# power-sheet.net
KiCad netlist of a schematic drawn in Altium Designer
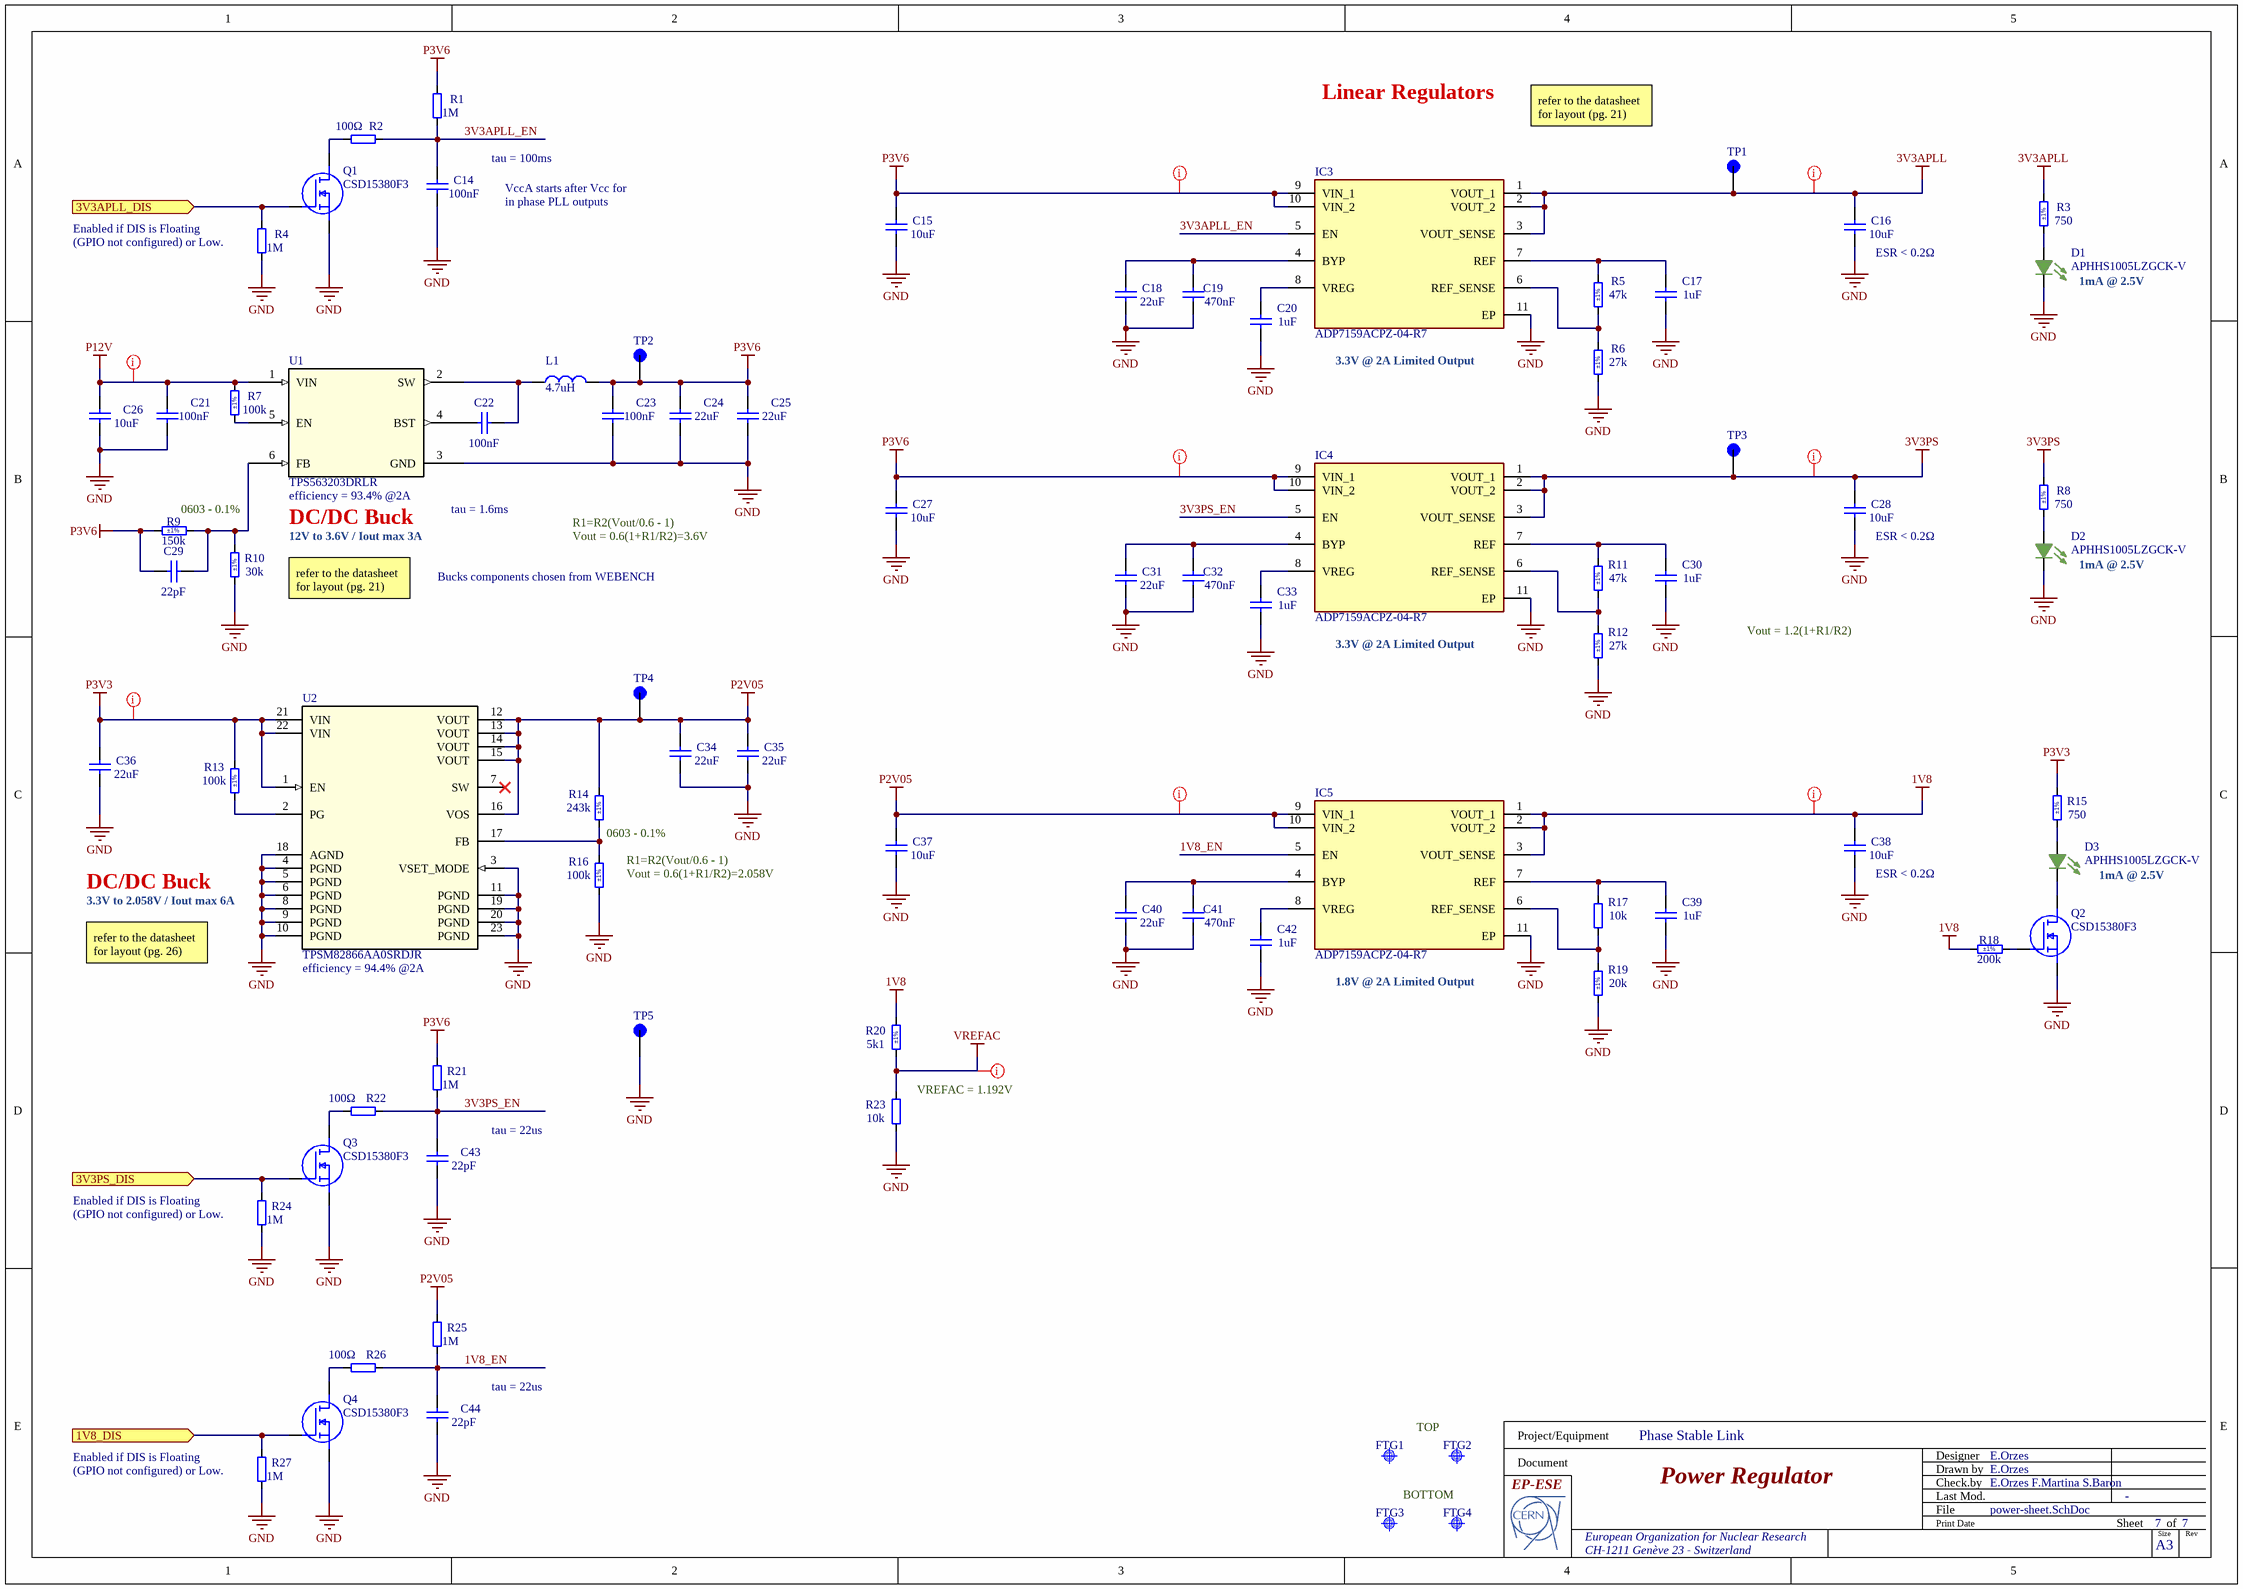
[diagram p0: power-sheet.SchDoc]

(export (version "E")
  (design (tool "Eeschema 10.0.6"))
  (components
    (comp (ref "C14")
      (value "100nF")
      (footprint "MURATA_HI_DENSITY_0201")
      (description "GRM033R61C104KE14")
      (libsource (lib "schLib") (part "C0201-100nF-high-density"))
    )
    (comp (ref "C15")
      (value "10uF")
      (footprint "CAPC1608X87N")
      (description "C1608X5R1E106M080AC")
      (fields
        (field (name "PART NUMBER") "CC0603_10UF_6.3V_20%_X5R")
        (field (name "VOLTAGE") "6.3V")
        (field (name "AUTHOR") "CERN DEM JLC")
      )
      (libsource (lib "Capacitors") (part "Capacitor - non polarized"))
    )
    (comp (ref "C16")
      (value "10uF")
      (footprint "CAPC1608X87N")
      (description "C1608X5R1E106M080AC")
      (fields
        (field (name "PART NUMBER") "CC0603_10UF_6.3V_20%_X5R")
        (field (name "VOLTAGE") "6.3V")
        (field (name "AUTHOR") "CERN DEM JLC")
      )
      (libsource (lib "Capacitors") (part "Capacitor - non polarized"))
    )
    (comp (ref "C17")
      (value "1uF")
      (footprint "CAPC1005X55N")
      (description "GRM153B30J105ME15")
      (fields
        (field (name "PART NUMBER") "CC0402_1UF_16V_10%_X5R")
        (field (name "VOLTAGE") "16V")
        (field (name "AUTHOR") "CERN DEM JLC")
      )
      (libsource (lib "Capacitors") (part "Capacitor - non polarized"))
    )
    (comp (ref "C18")
      (value "22uF")
      (footprint "MURATA_HI_DENSITY_0402_CAP")
      (description "GRM155R60J226ME11")
      (libsource (lib "schLib") (part "C0402-22uF-high-density"))
    )
    (comp (ref "C19")
      (value "470nF")
      (footprint "CAPC0510X04N")
      (description "LLL153C70G474ME17")
      (libsource (lib "auxiliary_library") (part "Capacitor - non polarized"))
    )
    (comp (ref "C20")
      (value "1uF")
      (footprint "CAPC1005X55N")
      (description "GRM153B30J105ME15")
      (fields
        (field (name "PART NUMBER") "CC0402_1UF_16V_10%_X5R")
        (field (name "VOLTAGE") "16V")
        (field (name "AUTHOR") "CERN DEM JLC")
      )
      (libsource (lib "Capacitors") (part "Capacitor - non polarized"))
    )
    (comp (ref "C21")
      (value "100nF")
      (footprint "MURATA_HI_DENSITY_0402_CAP")
      (description "GRM155R71E104KE14")
      (libsource (lib "schLib") (part "C0402-22uF-high-density"))
    )
    (comp (ref "C22")
      (value "100nF")
      (footprint "MURATA_HI_DENSITY_0402_CAP")
      (description "GRM155R71E104KE14")
      (libsource (lib "schLib") (part "C0402-22uF-high-density"))
    )
    (comp (ref "C23")
      (value "100nF")
      (footprint "MURATA_HI_DENSITY_0402_CAP")
      (description "GRM155R71E104KE14")
      (libsource (lib "schLib") (part "C0402-22uF-high-density"))
    )
    (comp (ref "C24")
      (value "22uF")
      (footprint "MURATA_HI_DENSITY_0402_CAP")
      (description "GRM155R60J226ME11")
      (libsource (lib "schLib") (part "C0402-22uF-high-density"))
    )
    (comp (ref "C25")
      (value "22uF")
      (footprint "MURATA_HI_DENSITY_0402_CAP")
      (description "GRM155R60J226ME11")
      (libsource (lib "schLib") (part "C0402-22uF-high-density"))
    )
    (comp (ref "C26")
      (value "10uF")
      (footprint "CAPC1608X87N")
      (description "C1608X5R1E106M080AC")
      (fields
        (field (name "PART NUMBER") "CC0603_10UF_6.3V_20%_X5R")
        (field (name "VOLTAGE") "6.3V")
        (field (name "AUTHOR") "CERN DEM JLC")
      )
      (libsource (lib "Capacitors") (part "Capacitor - non polarized"))
    )
    (comp (ref "C27")
      (value "10uF")
      (footprint "CAPC1608X87N")
      (description "C1608X5R1E106M080AC")
      (fields
        (field (name "PART NUMBER") "CC0603_10UF_6.3V_20%_X5R")
        (field (name "VOLTAGE") "6.3V")
        (field (name "AUTHOR") "CERN DEM JLC")
      )
      (libsource (lib "Capacitors") (part "Capacitor - non polarized"))
    )
    (comp (ref "C28")
      (value "10uF")
      (footprint "CAPC1608X87N")
      (description "C1608X5R1E106M080AC")
      (fields
        (field (name "PART NUMBER") "CC0603_10UF_6.3V_20%_X5R")
        (field (name "VOLTAGE") "6.3V")
        (field (name "AUTHOR") "CERN DEM JLC")
      )
      (libsource (lib "Capacitors") (part "Capacitor - non polarized"))
    )
    (comp (ref "C29")
      (value "22pF")
      (footprint "MURATA_HI_DENSITY_0402_CAP")
      (description "C0402C220J4GACTU")
      (libsource (lib "schLib") (part "C0402-22uF-high-density"))
    )
    (comp (ref "C30")
      (value "1uF")
      (footprint "CAPC1005X55N")
      (description "GRM153B30J105ME15")
      (fields
        (field (name "PART NUMBER") "CC0402_1UF_16V_10%_X5R")
        (field (name "VOLTAGE") "16V")
        (field (name "AUTHOR") "CERN DEM JLC")
      )
      (libsource (lib "Capacitors") (part "Capacitor - non polarized"))
    )
    (comp (ref "C31")
      (value "22uF")
      (footprint "MURATA_HI_DENSITY_0402_CAP")
      (description "GRM155R60J226ME11")
      (libsource (lib "schLib") (part "C0402-22uF-high-density"))
    )
    (comp (ref "C32")
      (value "470nF")
      (footprint "CAPC0510X04N")
      (description "LLL153C70G474ME17")
      (libsource (lib "auxiliary_library") (part "Capacitor - non polarized"))
    )
    (comp (ref "C33")
      (value "1uF")
      (footprint "CAPC1005X55N")
      (description "GRM153B30J105ME15")
      (fields
        (field (name "PART NUMBER") "CC0402_1UF_16V_10%_X5R")
        (field (name "VOLTAGE") "16V")
        (field (name "AUTHOR") "CERN DEM JLC")
      )
      (libsource (lib "Capacitors") (part "Capacitor - non polarized"))
    )
    (comp (ref "C34")
      (value "22uF")
      (footprint "MURATA_HI_DENSITY_0402_CAP")
      (description "GRM155R60J226ME11")
      (libsource (lib "schLib") (part "C0402-22uF-high-density"))
    )
    (comp (ref "C35")
      (value "22uF")
      (footprint "MURATA_HI_DENSITY_0402_CAP")
      (description "GRM155R60J226ME11")
      (libsource (lib "schLib") (part "C0402-22uF-high-density"))
    )
    (comp (ref "C36")
      (value "22uF")
      (footprint "MURATA_HI_DENSITY_0402_CAP")
      (description "GRM155R60J226ME11")
      (libsource (lib "schLib") (part "C0402-22uF-high-density"))
    )
    (comp (ref "C37")
      (value "10uF")
      (footprint "CAPC1608X87N")
      (description "C1608X5R1E106M080AC")
      (fields
        (field (name "PART NUMBER") "CC0603_10UF_6.3V_20%_X5R")
        (field (name "VOLTAGE") "6.3V")
        (field (name "AUTHOR") "CERN DEM JLC")
      )
      (libsource (lib "Capacitors") (part "Capacitor - non polarized"))
    )
    (comp (ref "C38")
      (value "10uF")
      (footprint "CAPC1608X87N")
      (description "C1608X5R1E106M080AC")
      (fields
        (field (name "PART NUMBER") "CC0603_10UF_6.3V_20%_X5R")
        (field (name "VOLTAGE") "6.3V")
        (field (name "AUTHOR") "CERN DEM JLC")
      )
      (libsource (lib "Capacitors") (part "Capacitor - non polarized"))
    )
    (comp (ref "C39")
      (value "1uF")
      (footprint "CAPC1005X55N")
      (description "GRM153B30J105ME15")
      (fields
        (field (name "PART NUMBER") "CC0402_1UF_16V_10%_X5R")
        (field (name "VOLTAGE") "16V")
        (field (name "AUTHOR") "CERN DEM JLC")
      )
      (libsource (lib "Capacitors") (part "Capacitor - non polarized"))
    )
    (comp (ref "C40")
      (value "22uF")
      (footprint "MURATA_HI_DENSITY_0402_CAP")
      (description "GRM155R60J226ME11")
      (libsource (lib "schLib") (part "C0402-22uF-high-density"))
    )
    (comp (ref "C41")
      (value "470nF")
      (footprint "CAPC0510X04N")
      (description "LLL153C70G474ME17")
      (libsource (lib "auxiliary_library") (part "Capacitor - non polarized"))
    )
    (comp (ref "C42")
      (value "1uF")
      (footprint "CAPC1005X55N")
      (description "GRM153B30J105ME15")
      (fields
        (field (name "PART NUMBER") "CC0402_1UF_16V_10%_X5R")
        (field (name "VOLTAGE") "16V")
        (field (name "AUTHOR") "CERN DEM JLC")
      )
      (libsource (lib "Capacitors") (part "Capacitor - non polarized"))
    )
    (comp (ref "C43")
      (value "22pF")
      (footprint "MURATA_HI_DENSITY_0402_CAP")
      (description "C0402C220J4GACTU")
      (libsource (lib "schLib") (part "C0402-22uF-high-density"))
    )
    (comp (ref "C44")
      (value "22pF")
      (footprint "MURATA_HI_DENSITY_0402_CAP")
      (description "C0402C220J4GACTU")
      (libsource (lib "schLib") (part "C0402-22uF-high-density"))
    )
    (comp (ref "D1")
      (value "APHHS1005LZGCK-V")
      (footprint "LED_APHHS1005LZGCK-V")
      (description "Led Green 0402 2mA 2.65V 40mcd 102mW")
      (fields (field (name "MF") "Kingbright Corporation"))
      (libsource (lib "APHHS1005LZGCK-V") (part "APHHS1005LZGCK-V"))
    )
    (comp (ref "D2")
      (value "APHHS1005LZGCK-V")
      (footprint "LED_APHHS1005LZGCK-V")
      (description "Led Green 0402 2mA 2.65V 40mcd 102mW")
      (fields (field (name "MF") "Kingbright Corporation"))
      (libsource (lib "APHHS1005LZGCK-V") (part "APHHS1005LZGCK-V"))
    )
    (comp (ref "D3")
      (value "APHHS1005LZGCK-V")
      (footprint "LED_APHHS1005LZGCK-V")
      (description "Led Green 0402 2mA 2.65V 40mcd 102mW")
      (fields (field (name "MF") "Kingbright Corporation"))
      (libsource (lib "APHHS1005LZGCK-V") (part "APHHS1005LZGCK-V"))
    )
    (comp (ref "FTG1")
      (value "Use only in PCB")
      (footprint "FIDUCIAL_TOP_C100-200")
      (description "Fiducial Target")
      (fields (field (name "PART NUMBER") "FIDUCIAL_TARGET_C100-200") (field (name "AUTHOR") "CERN DEM JLC"))
      (libsource (lib "Eletro-mechanical") (part "Fiducial Target"))
    )
    (comp (ref "FTG2")
      (value "Use only in PCB")
      (footprint "FIDUCIAL_TOP_C100-200")
      (description "Fiducial Target")
      (fields (field (name "PART NUMBER") "FIDUCIAL_TARGET_C100-200") (field (name "AUTHOR") "CERN DEM JLC"))
      (libsource (lib "Eletro-mechanical") (part "Fiducial Target"))
    )
    (comp (ref "FTG3")
      (value "Use only in PCB")
      (footprint "FIDUCIAL_TOP_C100-200")
      (description "Fiducial Target")
      (fields (field (name "PART NUMBER") "FIDUCIAL_TARGET_C100-200") (field (name "AUTHOR") "CERN DEM JLC"))
      (libsource (lib "Eletro-mechanical") (part "Fiducial Target"))
    )
    (comp (ref "FTG4")
      (value "Use only in PCB")
      (footprint "FIDUCIAL_TOP_C100-200")
      (description "Fiducial Target")
      (fields (field (name "PART NUMBER") "FIDUCIAL_TARGET_C100-200") (field (name "AUTHOR") "CERN DEM JLC"))
      (libsource (lib "Eletro-mechanical") (part "Fiducial Target"))
    )
    (comp (ref "IC3")
      (value "ADP7159ACPZ-04-R7")
      (footprint "SamacSys:SON50P300X300X85-11N-D")
      (description "Integrated Circuit")
      (fields (field (name "MOUSER PART NUMBER") "584-ADP7159ACPZ04R7"))
      (libsource (lib "SamacSys") (part "ADP7159ACPZ-04-R7"))
    )
    (comp (ref "IC4")
      (value "ADP7159ACPZ-04-R7")
      (footprint "SamacSys:SON50P300X300X85-11N-D")
      (description "Integrated Circuit")
      (fields (field (name "MOUSER PART NUMBER") "584-ADP7159ACPZ04R7"))
      (libsource (lib "SamacSys") (part "ADP7159ACPZ-04-R7"))
    )
    (comp (ref "IC5")
      (value "ADP7159ACPZ-04-R7")
      (footprint "SamacSys:SON50P300X300X85-11N-D")
      (description "Integrated Circuit")
      (fields (field (name "MOUSER PART NUMBER") "584-ADP7159ACPZ04R7"))
      (libsource (lib "SamacSys") (part "ADP7159ACPZ-04-R7"))
    )
    (comp (ref "L1")
      (value "4.7uH")
      (footprint "SamacSys:DFE322520FD1R0MP2")
      (description "Inductor")
      (fields
        (field (name "MANUFACTURER_PART_NUMBER") "DFE322520FD-4R7M=P2")
        (field (name "MOUSER PART NUMBER") "81-DFE322520FD4R7MP2")
      )
      (libsource (lib "SamacSys") (part "DFE322520FD-4R7M=P2"))
    )
    (comp (ref "Q1")
      (value "CSD15380F3")
      (footprint "SamacSys:CSD15380F3")
      (description "MOSFET (N-Channel)")
      (fields (field (name "MOUSER PART NUMBER") "595-CSD15380F3"))
      (libsource (lib "*") (part "CSD15380F3"))
    )
    (comp (ref "Q2")
      (value "CSD15380F3")
      (footprint "SamacSys:CSD15380F3")
      (description "MOSFET (N-Channel)")
      (fields (field (name "MOUSER PART NUMBER") "595-CSD15380F3"))
      (libsource (lib "*") (part "CSD15380F3"))
    )
    (comp (ref "Q3")
      (value "CSD15380F3")
      (footprint "SamacSys:CSD15380F3")
      (description "MOSFET (N-Channel)")
      (fields (field (name "MOUSER PART NUMBER") "595-CSD15380F3"))
      (libsource (lib "*") (part "CSD15380F3"))
    )
    (comp (ref "Q4")
      (value "CSD15380F3")
      (footprint "SamacSys:CSD15380F3")
      (description "MOSFET (N-Channel)")
      (fields (field (name "MOUSER PART NUMBER") "595-CSD15380F3"))
      (libsource (lib "*") (part "CSD15380F3"))
    )
    (comp (ref "R1")
      (value "1M")
      (footprint "MURATA_HI_DENSITY_0201")
      (description "Resistor 10k")
      (libsource (lib "schLib") (part "R0201-100ohm-high-density"))
    )
    (comp (ref "R2")
      (value "100Ω")
      (footprint "MURATA_HI_DENSITY_0201")
      (description "Resistor")
      (libsource (lib "schLib") (part "R0201-100ohm-high-density"))
    )
    (comp (ref "R3")
      (value "750")
      (footprint "RESC1005X40N")
      (description "Resistor - 1%")
      (fields
        (field (name "TOLERANCE") "±1%")
        (field (name "PART NUMBER") "R0402_750R_1%_0.0625W_100PPM")
        (field (name "POWER") "0.0625W")
        (field (name "AUTHOR") "CERN DEM JLC")
      )
      (libsource (lib "Resistors") (part "Resistor - 1%"))
    )
    (comp (ref "R4")
      (value "1M")
      (footprint "MURATA_HI_DENSITY_0201")
      (description "Resistor 10k")
      (libsource (lib "schLib") (part "R0201-100ohm-high-density"))
    )
    (comp (ref "R5")
      (value "47k")
      (footprint "RESC1005X40N")
      (description "Resistor - 1%")
      (fields
        (field (name "TOLERANCE") "±1%")
        (field (name "PART NUMBER") "R0402_47K_1%_0.0625W_100PPM")
        (field (name "POWER") "0.0625W")
        (field (name "AUTHOR") "CERN DEM JLC")
      )
      (libsource (lib "Resistors") (part "Resistor - 1%"))
    )
    (comp (ref "R6")
      (value "27k")
      (footprint "RESC1005X40N")
      (description "Resistor - 1%")
      (fields
        (field (name "TOLERANCE") "±1%")
        (field (name "PART NUMBER") "R0402_27K_1%_0.0625W_100PPM")
        (field (name "POWER") "0.0625W")
        (field (name "AUTHOR") "CERN DEM JLC")
      )
      (libsource (lib "Resistors") (part "Resistor - 1%"))
    )
    (comp (ref "R7")
      (value "100k")
      (footprint "RESC1608X55N")
      (description "Resistor - 1%")
      (fields
        (field (name "TOLERANCE") "±1%")
        (field (name "PART NUMBER") "R0603_30K_1%_0.1W_100PPM")
        (field (name "POWER") "0.1W")
        (field (name "AUTHOR") "CERN DEM JLC")
      )
      (libsource (lib "Resistors") (part "Resistor - 1%"))
    )
    (comp (ref "R8")
      (value "750")
      (footprint "RESC1005X40N")
      (description "Resistor - 1%")
      (fields
        (field (name "TOLERANCE") "±1%")
        (field (name "PART NUMBER") "R0402_750R_1%_0.0625W_100PPM")
        (field (name "POWER") "0.0625W")
        (field (name "AUTHOR") "CERN DEM JLC")
      )
      (libsource (lib "Resistors") (part "Resistor - 1%"))
    )
    (comp (ref "R9")
      (value "150k")
      (footprint "RESC1608X55N")
      (description "Resistor - 1%")
      (fields
        (field (name "TOLERANCE") "±1%")
        (field (name "PART NUMBER") "R0603_150K_1%_0.1W_100PPM")
        (field (name "POWER") "0.1W")
        (field (name "AUTHOR") "CERN DEM JLC")
      )
      (libsource (lib "Resistors") (part "Resistor - 1%"))
    )
    (comp (ref "R10")
      (value "30k")
      (footprint "RESC1608X55N")
      (description "Resistor - 1%")
      (fields
        (field (name "TOLERANCE") "±1%")
        (field (name "PART NUMBER") "R0603_30K_1%_0.1W_100PPM")
        (field (name "POWER") "0.1W")
        (field (name "AUTHOR") "CERN DEM JLC")
      )
      (libsource (lib "Resistors") (part "Resistor - 1%"))
    )
    (comp (ref "R11")
      (value "47k")
      (footprint "RESC1005X40N")
      (description "Resistor - 1%")
      (fields
        (field (name "TOLERANCE") "±1%")
        (field (name "PART NUMBER") "R0402_47K_1%_0.0625W_100PPM")
        (field (name "POWER") "0.0625W")
        (field (name "AUTHOR") "CERN DEM JLC")
      )
      (libsource (lib "Resistors") (part "Resistor - 1%"))
    )
    (comp (ref "R12")
      (value "27k")
      (footprint "RESC1005X40N")
      (description "Resistor - 1%")
      (fields
        (field (name "TOLERANCE") "±1%")
        (field (name "PART NUMBER") "R0402_27K_1%_0.0625W_100PPM")
        (field (name "POWER") "0.0625W")
        (field (name "AUTHOR") "CERN DEM JLC")
      )
      (libsource (lib "Resistors") (part "Resistor - 1%"))
    )
    (comp (ref "R13")
      (value "100k")
      (footprint "RESC1608X55N")
      (description "Resistor - 1%")
      (fields
        (field (name "TOLERANCE") "±1%")
        (field (name "PART NUMBER") "R0603_30K_1%_0.1W_100PPM")
        (field (name "POWER") "0.1W")
        (field (name "AUTHOR") "CERN DEM JLC")
      )
      (libsource (lib "Resistors") (part "Resistor - 1%"))
    )
    (comp (ref "R14")
      (value "243k")
      (footprint "RESC1608X55N")
      (description "Resistor - 1%")
      (fields
        (field (name "TOLERANCE") "±1%")
        (field (name "PART NUMBER") "R0603_30K_1%_0.1W_100PPM")
        (field (name "POWER") "0.1W")
        (field (name "AUTHOR") "CERN DEM JLC")
      )
      (libsource (lib "Resistors") (part "Resistor - 1%"))
    )
    (comp (ref "R15")
      (value "750")
      (footprint "RESC1005X40N")
      (description "Resistor - 1%")
      (fields
        (field (name "TOLERANCE") "±1%")
        (field (name "PART NUMBER") "R0402_750R_1%_0.0625W_100PPM")
        (field (name "POWER") "0.0625W")
        (field (name "AUTHOR") "CERN DEM JLC")
      )
      (libsource (lib "Resistors") (part "Resistor - 1%"))
    )
    (comp (ref "R16")
      (value "100k")
      (footprint "RESC1608X55N")
      (description "Resistor - 1%")
      (fields
        (field (name "TOLERANCE") "±1%")
        (field (name "PART NUMBER") "R0603_30K_1%_0.1W_100PPM")
        (field (name "POWER") "0.1W")
        (field (name "AUTHOR") "CERN DEM JLC")
      )
      (libsource (lib "Resistors") (part "Resistor - 1%"))
    )
    (comp (ref "R17")
      (value "10k")
      (footprint "MURATA_HI_DENSITY_0201")
      (description "Resistor 10k")
      (libsource (lib "schLib") (part "R0201-100ohm-high-density"))
    )
    (comp (ref "R18")
      (value "200k")
      (footprint "RESC1005X40N")
      (description "Resistor - 1%")
      (fields
        (field (name "TOLERANCE") "±1%")
        (field (name "PART NUMBER") "R0402_200K_1%_0.0625W_100PPM")
        (field (name "POWER") "0.0625W")
        (field (name "AUTHOR") "CERN DEM JLC")
      )
      (libsource (lib "Resistors") (part "Resistor - 1%"))
    )
    (comp (ref "R19")
      (value "20k")
      (footprint "RESC1005X40N")
      (description "Resistor - 1%")
      (fields
        (field (name "TOLERANCE") "±1%")
        (field (name "PART NUMBER") "R0402_20K_1%_0.0625W_100PPM")
        (field (name "POWER") "0.0625W")
        (field (name "AUTHOR") "CERN DEM JLC")
      )
      (libsource (lib "Resistors") (part "Resistor - 1%"))
    )
    (comp (ref "R20")
      (value "5k1")
      (footprint "RESC1005X40N")
      (description "Resistor - 1%")
      (fields
        (field (name "TOLERANCE") "±1%")
        (field (name "PART NUMBER") "R0402_5K1_1%_0.0625W_100PPM")
        (field (name "POWER") "0.0625W")
        (field (name "AUTHOR") "CERN DEM JLC")
      )
      (libsource (lib "Resistors") (part "Resistor - 1%"))
    )
    (comp (ref "R21")
      (value "1M")
      (footprint "MURATA_HI_DENSITY_0201")
      (description "Resistor 10k")
      (libsource (lib "schLib") (part "R0201-100ohm-high-density"))
    )
    (comp (ref "R22")
      (value "100Ω")
      (footprint "MURATA_HI_DENSITY_0201")
      (description "Resistor")
      (libsource (lib "schLib") (part "R0201-100ohm-high-density"))
    )
    (comp (ref "R23")
      (value "10k")
      (footprint "MURATA_HI_DENSITY_0201")
      (description "Resistor 10k")
      (libsource (lib "schLib") (part "R0201-100ohm-high-density"))
    )
    (comp (ref "R24")
      (value "1M")
      (footprint "MURATA_HI_DENSITY_0201")
      (description "Resistor 10k")
      (libsource (lib "schLib") (part "R0201-100ohm-high-density"))
    )
    (comp (ref "R25")
      (value "1M")
      (footprint "MURATA_HI_DENSITY_0201")
      (description "Resistor 10k")
      (libsource (lib "schLib") (part "R0201-100ohm-high-density"))
    )
    (comp (ref "R26")
      (value "100Ω")
      (footprint "MURATA_HI_DENSITY_0201")
      (description "Resistor")
      (libsource (lib "schLib") (part "R0201-100ohm-high-density"))
    )
    (comp (ref "R27")
      (value "1M")
      (footprint "MURATA_HI_DENSITY_0201")
      (description "Resistor 10k")
      (libsource (lib "schLib") (part "R0201-100ohm-high-density"))
    )
    (comp (ref "TP1")
      (value "RCU-0C")
      (footprint "TP+195X110")
      (fields (field (name "MF") "{'manufacturer': u'TE Connectivity AMP Connectors'}"))
      (libsource (lib "RCU-0C") (part "RCU-0C"))
    )
    (comp (ref "TP2")
      (value "RCU-0C")
      (footprint "TP+195X110")
      (fields (field (name "MF") "{'manufacturer': u'TE Connectivity AMP Connectors'}"))
      (libsource (lib "RCU-0C") (part "RCU-0C"))
    )
    (comp (ref "TP3")
      (value "RCU-0C")
      (footprint "TP+195X110")
      (fields (field (name "MF") "{'manufacturer': u'TE Connectivity AMP Connectors'}"))
      (libsource (lib "RCU-0C") (part "RCU-0C"))
    )
    (comp (ref "TP4")
      (value "RCU-0C")
      (footprint "TP+195X110")
      (fields (field (name "MF") "{'manufacturer': u'TE Connectivity AMP Connectors'}"))
      (libsource (lib "RCU-0C") (part "RCU-0C"))
    )
    (comp (ref "TP5")
      (value "RCU-0C")
      (footprint "TP+195X110")
      (fields (field (name "MF") "{'manufacturer': u'TE Connectivity AMP Connectors'}"))
      (libsource (lib "RCU-0C") (part "RCU-0C"))
    )
    (comp (ref "U1")
      (value "TPS563203DRLR")
      (footprint "TPS563203DRLR:SOT_07SDRLR_TEX")
      (description "No Description Available")
      (libsource (lib "TPS563203DRLR") (part "TPS563203DRLR"))
    )
    (comp (ref "U2")
      (value "TPSM82866AA0SRDJR")
      (footprint "RDJ0023A-MFG")
      (description "No Description Available")
      (libsource (lib "XPSM82866AA0SRDJR") (part "XPSM82866AA0SRDJR"))
    )
  )
  (nets
    (net (code "1") (name "/1V8_DIS") (class "Default")
      (node (ref "Q4") (pin "1") (pinfunction "G_1") (pintype "passive"))
      (node (ref "R27") (pin "1") (pinfunction "1_1") (pintype "passive"))
    )
    (net (code "2") (name "/1V8_EN") (class "Default")
      (node (ref "C44") (pin "1") (pinfunction "1_1") (pintype "passive"))
      (node (ref "IC5") (pin "5") (pinfunction "EN_5") (pintype "passive"))
      (node (ref "R25") (pin "2") (pinfunction "2_2") (pintype "passive"))
      (node (ref "R26") (pin "2") (pinfunction "2_2") (pintype "passive"))
    )
    (net (code "3") (name "/3V3APLL_DIS") (class "Default")
      (node (ref "Q1") (pin "1") (pinfunction "G_1") (pintype "passive"))
      (node (ref "R4") (pin "1") (pinfunction "1_1") (pintype "passive"))
    )
    (net (code "4") (name "/3V3APLL_EN") (class "Default")
      (node (ref "C14") (pin "2") (pinfunction "2_2") (pintype "passive"))
      (node (ref "IC3") (pin "5") (pinfunction "EN_5") (pintype "passive"))
      (node (ref "R1") (pin "2") (pinfunction "2_2") (pintype "passive"))
      (node (ref "R2") (pin "2") (pinfunction "2_2") (pintype "passive"))
    )
    (net (code "5") (name "/3V3PS_DIS") (class "Default")
      (node (ref "Q3") (pin "1") (pinfunction "G_1") (pintype "passive"))
      (node (ref "R24") (pin "1") (pinfunction "1_1") (pintype "passive"))
    )
    (net (code "6") (name "/3V3PS_EN") (class "Default")
      (node (ref "C43") (pin "1") (pinfunction "1_1") (pintype "passive"))
      (node (ref "IC4") (pin "5") (pinfunction "EN_5") (pintype "passive"))
      (node (ref "R21") (pin "2") (pinfunction "2_2") (pintype "passive"))
      (node (ref "R22") (pin "2") (pinfunction "2_2") (pintype "passive"))
    )
    (net (code "7") (name "1V8") (class "Default")
      (node (ref "C38") (pin "2") (pinfunction "2_2") (pintype "passive"))
      (node (ref "IC5") (pin "1") (pinfunction "VOUT_1_1") (pintype "passive"))
      (node (ref "IC5") (pin "2") (pinfunction "VOUT_2_2") (pintype "passive"))
      (node (ref "IC5") (pin "3") (pinfunction "VOUT_SENSE_3") (pintype "passive"))
      (node (ref "R18") (pin "1") (pinfunction "1_1") (pintype "passive"))
      (node (ref "R20") (pin "2") (pinfunction "2_2") (pintype "passive"))
    )
    (net (code "8") (name "3V3APLL") (class "Default")
      (node (ref "C16") (pin "2") (pinfunction "2_2") (pintype "passive"))
      (node (ref "IC3") (pin "1") (pinfunction "VOUT_1_1") (pintype "passive"))
      (node (ref "IC3") (pin "2") (pinfunction "VOUT_2_2") (pintype "passive"))
      (node (ref "IC3") (pin "3") (pinfunction "VOUT_SENSE_3") (pintype "passive"))
      (node (ref "R3") (pin "2") (pinfunction "2_2") (pintype "passive"))
      (node (ref "TP1") (pin "1") (pinfunction "TP_1") (pintype "passive"))
    )
    (net (code "9") (name "3V3PS") (class "Default")
      (node (ref "C28") (pin "2") (pinfunction "2_2") (pintype "passive"))
      (node (ref "IC4") (pin "1") (pinfunction "VOUT_1_1") (pintype "passive"))
      (node (ref "IC4") (pin "2") (pinfunction "VOUT_2_2") (pintype "passive"))
      (node (ref "IC4") (pin "3") (pinfunction "VOUT_SENSE_3") (pintype "passive"))
      (node (ref "R8") (pin "2") (pinfunction "2_2") (pintype "passive"))
      (node (ref "TP3") (pin "1") (pinfunction "TP_1") (pintype "passive"))
    )
    (net (code "10") (name "GND") (class "Default")
      (node (ref "C14") (pin "1") (pinfunction "1_1") (pintype "passive"))
      (node (ref "C15") (pin "1") (pinfunction "1_1") (pintype "passive"))
      (node (ref "C16") (pin "1") (pinfunction "1_1") (pintype "passive"))
      (node (ref "C17") (pin "1") (pinfunction "1_1") (pintype "passive"))
      (node (ref "C18") (pin "1") (pinfunction "1_1") (pintype "passive"))
      (node (ref "C19") (pin "1") (pinfunction "1_1") (pintype "passive"))
      (node (ref "C20") (pin "1") (pinfunction "1_1") (pintype "passive"))
      (node (ref "C21") (pin "2") (pinfunction "2_2") (pintype "passive"))
      (node (ref "C23") (pin "2") (pinfunction "2_2") (pintype "passive"))
      (node (ref "C24") (pin "1") (pinfunction "1_1") (pintype "passive"))
      (node (ref "C25") (pin "1") (pinfunction "1_1") (pintype "passive"))
      (node (ref "C26") (pin "1") (pinfunction "1_1") (pintype "passive"))
      (node (ref "C27") (pin "1") (pinfunction "1_1") (pintype "passive"))
      (node (ref "C28") (pin "1") (pinfunction "1_1") (pintype "passive"))
      (node (ref "C30") (pin "1") (pinfunction "1_1") (pintype "passive"))
      (node (ref "C31") (pin "1") (pinfunction "1_1") (pintype "passive"))
      (node (ref "C32") (pin "1") (pinfunction "1_1") (pintype "passive"))
      (node (ref "C33") (pin "1") (pinfunction "1_1") (pintype "passive"))
      (node (ref "C34") (pin "1") (pinfunction "1_1") (pintype "passive"))
      (node (ref "C35") (pin "1") (pinfunction "1_1") (pintype "passive"))
      (node (ref "C36") (pin "1") (pinfunction "1_1") (pintype "passive"))
      (node (ref "C37") (pin "1") (pinfunction "1_1") (pintype "passive"))
      (node (ref "C38") (pin "1") (pinfunction "1_1") (pintype "passive"))
      (node (ref "C39") (pin "1") (pinfunction "1_1") (pintype "passive"))
      (node (ref "C40") (pin "1") (pinfunction "1_1") (pintype "passive"))
      (node (ref "C41") (pin "1") (pinfunction "1_1") (pintype "passive"))
      (node (ref "C42") (pin "1") (pinfunction "1_1") (pintype "passive"))
      (node (ref "C43") (pin "2") (pinfunction "2_2") (pintype "passive"))
      (node (ref "C44") (pin "2") (pinfunction "2_2") (pintype "passive"))
      (node (ref "D1") (pin "1") (pinfunction "C_1") (pintype "passive"))
      (node (ref "D2") (pin "1") (pinfunction "C_1") (pintype "passive"))
      (node (ref "IC3") (pin "11") (pinfunction "EP_11") (pintype "passive"))
      (node (ref "IC4") (pin "11") (pinfunction "EP_11") (pintype "passive"))
      (node (ref "IC5") (pin "11") (pinfunction "EP_11") (pintype "passive"))
      (node (ref "Q1") (pin "2") (pinfunction "S_2") (pintype "passive"))
      (node (ref "Q2") (pin "2") (pinfunction "S_2") (pintype "passive"))
      (node (ref "Q3") (pin "2") (pinfunction "S_2") (pintype "passive"))
      (node (ref "Q4") (pin "2") (pinfunction "S_2") (pintype "passive"))
      (node (ref "R10") (pin "1") (pinfunction "1_1") (pintype "passive"))
      (node (ref "R12") (pin "1") (pinfunction "1_1") (pintype "passive"))
      (node (ref "R16") (pin "1") (pinfunction "1_1") (pintype "passive"))
      (node (ref "R19") (pin "1") (pinfunction "1_1") (pintype "passive"))
      (node (ref "R23") (pin "1") (pinfunction "1_1") (pintype "passive"))
      (node (ref "R24") (pin "2") (pinfunction "2_2") (pintype "passive"))
      (node (ref "R27") (pin "2") (pinfunction "2_2") (pintype "passive"))
      (node (ref "R4") (pin "2") (pinfunction "2_2") (pintype "passive"))
      (node (ref "R6") (pin "1") (pinfunction "1_1") (pintype "passive"))
      (node (ref "TP5") (pin "1") (pinfunction "TP_1") (pintype "passive"))
      (node (ref "U1") (pin "3") (pinfunction "GND_3") (pintype "power_in"))
      (node (ref "U2") (pin "10") (pinfunction "PGND_10") (pintype "power_in"))
      (node (ref "U2") (pin "11") (pinfunction "PGND_11") (pintype "power_in"))
      (node (ref "U2") (pin "18") (pinfunction "AGND_18") (pintype "power_in"))
      (node (ref "U2") (pin "19") (pinfunction "PGND_19") (pintype "power_in"))
      (node (ref "U2") (pin "20") (pinfunction "PGND_20") (pintype "power_in"))
      (node (ref "U2") (pin "23") (pinfunction "PGND_23") (pintype "power_in"))
      (node (ref "U2") (pin "3") (pinfunction "VSET_MODE_3") (pintype "input"))
      (node (ref "U2") (pin "4") (pinfunction "PGND_4") (pintype "power_in"))
      (node (ref "U2") (pin "5") (pinfunction "PGND_5") (pintype "power_in"))
      (node (ref "U2") (pin "6") (pinfunction "PGND_6") (pintype "power_in"))
      (node (ref "U2") (pin "8") (pinfunction "PGND_8") (pintype "power_in"))
      (node (ref "U2") (pin "9") (pinfunction "PGND_9") (pintype "power_in"))
    )
    (net (code "11") (name "Net-(D1-A)") (class "Default")
      (node (ref "D1") (pin "2") (pinfunction "A_2") (pintype "passive"))
      (node (ref "R3") (pin "1") (pinfunction "1_1") (pintype "passive"))
    )
    (net (code "12") (name "Net-(D2-A)") (class "Default")
      (node (ref "D2") (pin "2") (pinfunction "A_2") (pintype "passive"))
      (node (ref "R8") (pin "1") (pinfunction "1_1") (pintype "passive"))
    )
    (net (code "13") (name "Net-(D3-A)") (class "Default")
      (node (ref "D3") (pin "2") (pinfunction "A_2") (pintype "passive"))
      (node (ref "R15") (pin "1") (pinfunction "1_1") (pintype "passive"))
    )
    (net (code "14") (name "Net-(D3-C)") (class "Default")
      (node (ref "D3") (pin "1") (pinfunction "C_1") (pintype "passive"))
      (node (ref "Q2") (pin "3") (pinfunction "D_3") (pintype "passive"))
    )
    (net (code "15") (name "Net-(IC3-BYP)") (class "Default")
      (node (ref "C18") (pin "2") (pinfunction "2_2") (pintype "passive"))
      (node (ref "C19") (pin "2") (pinfunction "2_2") (pintype "passive"))
      (node (ref "IC3") (pin "4") (pinfunction "BYP_4") (pintype "passive"))
    )
    (net (code "16") (name "Net-(IC3-REF)") (class "Default")
      (node (ref "C17") (pin "2") (pinfunction "2_2") (pintype "passive"))
      (node (ref "IC3") (pin "7") (pinfunction "REF_7") (pintype "passive"))
      (node (ref "R5") (pin "2") (pinfunction "2_2") (pintype "passive"))
    )
    (net (code "17") (name "Net-(IC3-REF_SENSE)") (class "Default")
      (node (ref "IC3") (pin "6") (pinfunction "REF_SENSE_6") (pintype "passive"))
      (node (ref "R5") (pin "1") (pinfunction "1_1") (pintype "passive"))
      (node (ref "R6") (pin "2") (pinfunction "2_2") (pintype "passive"))
    )
    (net (code "18") (name "Net-(IC3-VREG)") (class "Default")
      (node (ref "C20") (pin "2") (pinfunction "2_2") (pintype "passive"))
      (node (ref "IC3") (pin "8") (pinfunction "VREG_8") (pintype "passive"))
    )
    (net (code "19") (name "Net-(IC4-BYP)") (class "Default")
      (node (ref "C31") (pin "2") (pinfunction "2_2") (pintype "passive"))
      (node (ref "C32") (pin "2") (pinfunction "2_2") (pintype "passive"))
      (node (ref "IC4") (pin "4") (pinfunction "BYP_4") (pintype "passive"))
    )
    (net (code "20") (name "Net-(IC4-REF)") (class "Default")
      (node (ref "C30") (pin "2") (pinfunction "2_2") (pintype "passive"))
      (node (ref "IC4") (pin "7") (pinfunction "REF_7") (pintype "passive"))
      (node (ref "R11") (pin "2") (pinfunction "2_2") (pintype "passive"))
    )
    (net (code "21") (name "Net-(IC4-REF_SENSE)") (class "Default")
      (node (ref "IC4") (pin "6") (pinfunction "REF_SENSE_6") (pintype "passive"))
      (node (ref "R11") (pin "1") (pinfunction "1_1") (pintype "passive"))
      (node (ref "R12") (pin "2") (pinfunction "2_2") (pintype "passive"))
    )
    (net (code "22") (name "Net-(IC4-VREG)") (class "Default")
      (node (ref "C33") (pin "2") (pinfunction "2_2") (pintype "passive"))
      (node (ref "IC4") (pin "8") (pinfunction "VREG_8") (pintype "passive"))
    )
    (net (code "23") (name "Net-(IC5-BYP)") (class "Default")
      (node (ref "C40") (pin "2") (pinfunction "2_2") (pintype "passive"))
      (node (ref "C41") (pin "2") (pinfunction "2_2") (pintype "passive"))
      (node (ref "IC5") (pin "4") (pinfunction "BYP_4") (pintype "passive"))
    )
    (net (code "24") (name "Net-(IC5-REF)") (class "Default")
      (node (ref "C39") (pin "2") (pinfunction "2_2") (pintype "passive"))
      (node (ref "IC5") (pin "7") (pinfunction "REF_7") (pintype "passive"))
      (node (ref "R17") (pin "2") (pinfunction "2_2") (pintype "passive"))
    )
    (net (code "25") (name "Net-(IC5-REF_SENSE)") (class "Default")
      (node (ref "IC5") (pin "6") (pinfunction "REF_SENSE_6") (pintype "passive"))
      (node (ref "R17") (pin "1") (pinfunction "1_1") (pintype "passive"))
      (node (ref "R19") (pin "2") (pinfunction "2_2") (pintype "passive"))
    )
    (net (code "26") (name "Net-(IC5-VREG)") (class "Default")
      (node (ref "C42") (pin "2") (pinfunction "2_2") (pintype "passive"))
      (node (ref "IC5") (pin "8") (pinfunction "VREG_8") (pintype "passive"))
    )
    (net (code "27") (name "Net-(Q1-D)") (class "Default")
      (node (ref "Q1") (pin "3") (pinfunction "D_3") (pintype "passive"))
      (node (ref "R2") (pin "1") (pinfunction "1_1") (pintype "passive"))
    )
    (net (code "28") (name "Net-(Q2-G)") (class "Default")
      (node (ref "Q2") (pin "1") (pinfunction "G_1") (pintype "passive"))
      (node (ref "R18") (pin "2") (pinfunction "2_2") (pintype "passive"))
    )
    (net (code "29") (name "Net-(Q3-D)") (class "Default")
      (node (ref "Q3") (pin "3") (pinfunction "D_3") (pintype "passive"))
      (node (ref "R22") (pin "1") (pinfunction "1_1") (pintype "passive"))
    )
    (net (code "30") (name "Net-(Q4-D)") (class "Default")
      (node (ref "Q4") (pin "3") (pinfunction "D_3") (pintype "passive"))
      (node (ref "R26") (pin "1") (pinfunction "1_1") (pintype "passive"))
    )
    (net (code "31") (name "Net-(U1-BST)") (class "Default")
      (node (ref "C22") (pin "2") (pinfunction "2_2") (pintype "passive"))
      (node (ref "U1") (pin "4") (pinfunction "BST_4") (pintype "output"))
    )
    (net (code "32") (name "Net-(U1-EN)") (class "Default")
      (node (ref "R7") (pin "1") (pinfunction "1_1") (pintype "passive"))
      (node (ref "U1") (pin "5") (pinfunction "EN_5") (pintype "input"))
    )
    (net (code "33") (name "Net-(U1-FB)") (class "Default")
      (node (ref "C29") (pin "1") (pinfunction "1_1") (pintype "passive"))
      (node (ref "R10") (pin "2") (pinfunction "2_2") (pintype "passive"))
      (node (ref "R9") (pin "2") (pinfunction "2_2") (pintype "passive"))
      (node (ref "U1") (pin "6") (pinfunction "FB_6") (pintype "input"))
    )
    (net (code "34") (name "Net-(U1-SW)") (class "Default")
      (node (ref "C22") (pin "1") (pinfunction "1_1") (pintype "passive"))
      (node (ref "L1") (pin "1") (pinfunction "1_1") (pintype "passive"))
      (node (ref "U1") (pin "2") (pinfunction "SW_2") (pintype "output"))
    )
    (net (code "35") (name "Net-(U2-FB)") (class "Default")
      (node (ref "R14") (pin "1") (pinfunction "1_1") (pintype "passive"))
      (node (ref "R16") (pin "2") (pinfunction "2_2") (pintype "passive"))
      (node (ref "U2") (pin "17") (pinfunction "FB_17") (pintype "passive"))
    )
    (net (code "36") (name "Net-(U2-PG)") (class "Default")
      (node (ref "R13") (pin "1") (pinfunction "1_1") (pintype "passive"))
      (node (ref "U2") (pin "2") (pinfunction "PG_2") (pintype "open_collector"))
    )
    (net (code "37") (name "P2V05") (class "Default")
      (node (ref "C34") (pin "2") (pinfunction "2_2") (pintype "passive"))
      (node (ref "C35") (pin "2") (pinfunction "2_2") (pintype "passive"))
      (node (ref "C37") (pin "2") (pinfunction "2_2") (pintype "passive"))
      (node (ref "IC5") (pin "10") (pinfunction "VIN_2_10") (pintype "passive"))
      (node (ref "IC5") (pin "9") (pinfunction "VIN_1_9") (pintype "passive"))
      (node (ref "R14") (pin "2") (pinfunction "2_2") (pintype "passive"))
      (node (ref "R25") (pin "1") (pinfunction "1_1") (pintype "passive"))
      (node (ref "TP4") (pin "1") (pinfunction "TP_1") (pintype "passive"))
      (node (ref "U2") (pin "12") (pinfunction "VOUT_12") (pintype "passive"))
      (node (ref "U2") (pin "13") (pinfunction "VOUT_13") (pintype "passive"))
      (node (ref "U2") (pin "14") (pinfunction "VOUT_14") (pintype "passive"))
      (node (ref "U2") (pin "15") (pinfunction "VOUT_15") (pintype "passive"))
      (node (ref "U2") (pin "16") (pinfunction "VOS_16") (pintype "passive"))
    )
    (net (code "38") (name "P3V3") (class "Default")
      (node (ref "C36") (pin "2") (pinfunction "2_2") (pintype "passive"))
      (node (ref "R13") (pin "2") (pinfunction "2_2") (pintype "passive"))
      (node (ref "R15") (pin "2") (pinfunction "2_2") (pintype "passive"))
      (node (ref "U2") (pin "1") (pinfunction "EN_1") (pintype "input"))
      (node (ref "U2") (pin "21") (pinfunction "VIN_21") (pintype "power_in"))
      (node (ref "U2") (pin "22") (pinfunction "VIN_22") (pintype "power_in"))
    )
    (net (code "39") (name "P3V6") (class "Default")
      (node (ref "C15") (pin "2") (pinfunction "2_2") (pintype "passive"))
      (node (ref "C23") (pin "1") (pinfunction "1_1") (pintype "passive"))
      (node (ref "C24") (pin "2") (pinfunction "2_2") (pintype "passive"))
      (node (ref "C25") (pin "2") (pinfunction "2_2") (pintype "passive"))
      (node (ref "C27") (pin "2") (pinfunction "2_2") (pintype "passive"))
      (node (ref "C29") (pin "2") (pinfunction "2_2") (pintype "passive"))
      (node (ref "IC3") (pin "10") (pinfunction "VIN_2_10") (pintype "passive"))
      (node (ref "IC3") (pin "9") (pinfunction "VIN_1_9") (pintype "passive"))
      (node (ref "IC4") (pin "10") (pinfunction "VIN_2_10") (pintype "passive"))
      (node (ref "IC4") (pin "9") (pinfunction "VIN_1_9") (pintype "passive"))
      (node (ref "L1") (pin "2") (pinfunction "2_2") (pintype "passive"))
      (node (ref "R1") (pin "1") (pinfunction "1_1") (pintype "passive"))
      (node (ref "R21") (pin "1") (pinfunction "1_1") (pintype "passive"))
      (node (ref "R9") (pin "1") (pinfunction "1_1") (pintype "passive"))
      (node (ref "TP2") (pin "1") (pinfunction "TP_1") (pintype "passive"))
    )
    (net (code "40") (name "P12V") (class "Default")
      (node (ref "C21") (pin "1") (pinfunction "1_1") (pintype "passive"))
      (node (ref "C26") (pin "2") (pinfunction "2_2") (pintype "passive"))
      (node (ref "R7") (pin "2") (pinfunction "2_2") (pintype "passive"))
      (node (ref "U1") (pin "1") (pinfunction "VIN_1") (pintype "input"))
    )
    (net (code "41") (name "VREFAC") (class "Default")
      (node (ref "R20") (pin "1") (pinfunction "1_1") (pintype "passive"))
      (node (ref "R23") (pin "2") (pinfunction "2_2") (pintype "passive"))
    )
    (net (code "42") (name "unconnected-(U2-SW-Pad7)") (class "Default")
      (node (ref "U2") (pin "7") (pinfunction "SW_7") (pintype "passive+no_connect"))
    )
  )
)
